# bitslot.net
KiCad netlist of a schematic drawn in Altium Designer
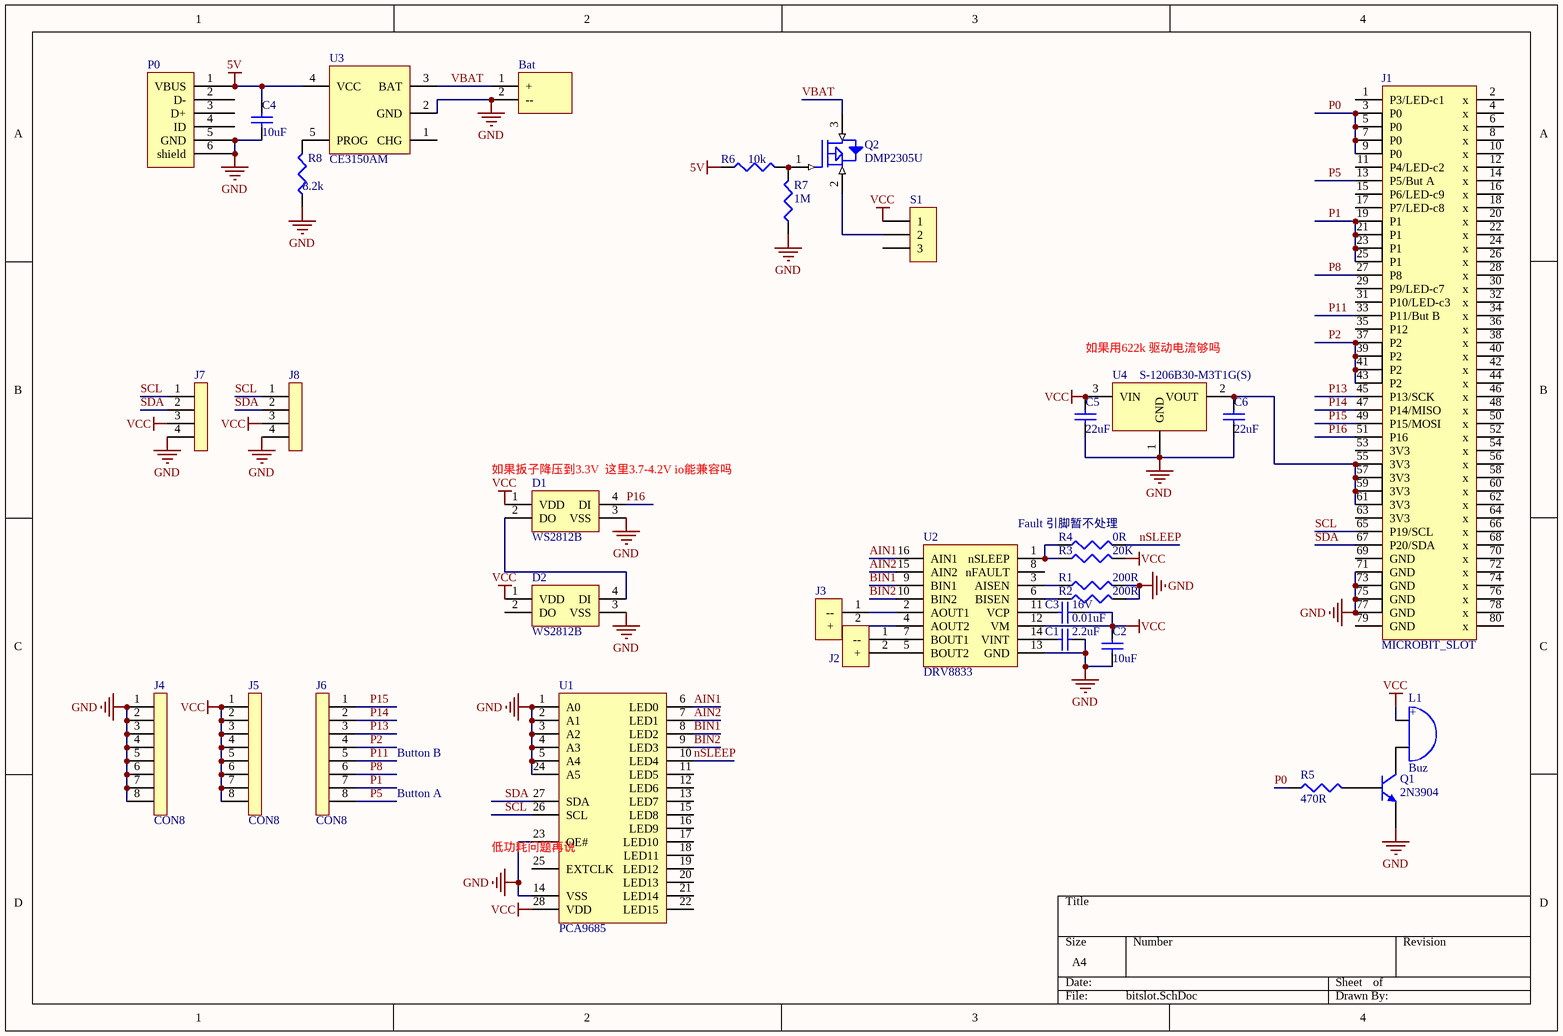
[diagram p0: bitslot.SchDoc]

(export (version "E")
  (design (tool "Eeschema 10.0.6"))
  (components
    (comp (ref "Bat")
      (value "~")
      (footprint "BAT-2040")
      (description "2x4cm Li-bat")
      (libsource (lib "misc1") (part "Battery2040"))
    )
    (comp (ref "C1")
      (value "2.2uF")
      (footprint "C0603")
      (fields (field (name "PUBLISHER") "Altium Limited"))
      (libsource (lib "misc") (part "Cap"))
    )
    (comp (ref "C2")
      (value "10uF")
      (footprint "C0603")
      (fields (field (name "PUBLISHER") "Altium Limited"))
      (libsource (lib "misc") (part "Cap"))
    )
    (comp (ref "C3")
      (value "16V")
      (footprint "C0603")
      (fields (field (name "ALTIUM_VALUE") "0.01uF") (field (name "PUBLISHER") "Altium Limited"))
      (libsource (lib "misc") (part "Cap"))
    )
    (comp (ref "C4")
      (value "10uF")
      (footprint "C0603")
      (fields (field (name "PUBLISHER") "Altium Limited"))
      (libsource (lib "misc") (part "Cap"))
    )
    (comp (ref "C5")
      (value "22uF")
      (footprint "C0603")
      (fields (field (name "PUBLISHER") "Altium Limited"))
      (libsource (lib "misc") (part "Cap"))
    )
    (comp (ref "C6")
      (value "22uF")
      (footprint "C0603")
      (fields (field (name "PUBLISHER") "Altium Limited"))
      (libsource (lib "misc") (part "Cap"))
    )
    (comp (ref "D1") (value "WS2812B") (footprint "WS2812B") (libsource (lib "misc1") (part "WS2812B")))
    (comp (ref "D2") (value "WS2812B") (footprint "WS2812B") (libsource (lib "misc1") (part "WS2812B")))
    (comp (ref "J1")
      (value "MICROBIT_SLOT")
      (footprint "microbit_slot")
      (libsource (lib "misc1") (part "MICROBIT_SLOT"))
    )
    (comp (ref "J2") (value "~") (footprint "S2B-PH-K-S") (libsource (lib "misc") (part "CON2_power")))
    (comp (ref "J3") (value "~") (footprint "S2B-PH-K-S") (libsource (lib "misc") (part "CON2_power")))
    (comp (ref "J4") (value "CON8") (footprint "CON8") (libsource (lib "misc") (part "CON8")))
    (comp (ref "J5") (value "CON8") (footprint "CON8") (libsource (lib "misc") (part "CON8")))
    (comp (ref "J6") (value "CON8") (footprint "CON8") (libsource (lib "") (part "CON8_1")))
    (comp (ref "J7") (value "~") (footprint "CON4") (libsource (lib "misc") (part "CON4")))
    (comp (ref "J8") (value "~") (footprint "CON4") (libsource (lib "misc") (part "CON4")))
    (comp (ref "L1")
      (value "Buz")
      (footprint "Buzzer")
      (fields (field (name "PUBLISHER") "Altium Limited"))
      (libsource (lib "misc") (part "Buzzer"))
    )
    (comp (ref "P0") (value "~") (footprint "USB_MICRO") (libsource (lib "Switcher") (part "micro_usb")))
    (comp (ref "Q1")
      (value "2N3904")
      (footprint "SOT23-3")
      (description "NPN General Purpose Amplifier")
      (fields (field (name "PUBLISHER") "Altium Limited"))
      (libsource (lib "misc") (part "2N3904"))
    )
    (comp (ref "Q2") (value "DMP2305U") (footprint "SOT23-3") (libsource (lib "misc") (part "MOSFET P")))
    (comp (ref "R1")
      (value "200R")
      (footprint "R0603")
      (fields (field (name "PUBLISHER") "Altium Limited"))
      (libsource (lib "misc") (part "Res"))
    )
    (comp (ref "R2")
      (value "200R")
      (footprint "R0603")
      (fields (field (name "PUBLISHER") "Altium Limited"))
      (libsource (lib "misc") (part "Res"))
    )
    (comp (ref "R3")
      (value "20K")
      (footprint "R0603")
      (fields (field (name "PUBLISHER") "Altium Limited"))
      (libsource (lib "misc") (part "Res"))
    )
    (comp (ref "R4")
      (value "0R")
      (footprint "R0603")
      (fields (field (name "PUBLISHER") "Altium Limited"))
      (libsource (lib "misc") (part "Res"))
    )
    (comp (ref "R5")
      (value "470R")
      (footprint "R0603")
      (fields (field (name "PUBLISHER") "Altium Limited"))
      (libsource (lib "misc") (part "Res"))
    )
    (comp (ref "R6")
      (value "10k")
      (footprint "R0603")
      (fields (field (name "PUBLISHER") "Altium Limited"))
      (libsource (lib "misc") (part "Res"))
    )
    (comp (ref "R7")
      (value "1M")
      (footprint "R0603")
      (fields (field (name "PUBLISHER") "Altium Limited"))
      (libsource (lib "misc") (part "Res"))
    )
    (comp (ref "R8")
      (value "8.2k")
      (footprint "R0603")
      (fields (field (name "PUBLISHER") "Altium Limited"))
      (libsource (lib "misc") (part "Res"))
    )
    (comp (ref "S1")
      (value "~")
      (footprint "SWITCH-1")
      (description "Header, 3-Pin")
      (fields (field (name "PUBLISHER") "Altium Limited"))
      (libsource (lib "misc") (part "CON3"))
    )
    (comp (ref "U1") (value "PCA9685") (footprint "TSSOP-28") (libsource (lib "misc1") (part "PCA9685")))
    (comp (ref "U2")
      (value "DRV8833")
      (footprint "TSSOP-16")
      (description "TSSOP-16")
      (libsource (lib "misc1") (part "DRV8833"))
    )
    (comp (ref "U3")
      (value "CE3150AM")
      (footprint "SOT23-5")
      (description "LI-Ion battery charger with Thermal Regulation")
      (libsource (lib "misc") (part "CE3150AM"))
    )
    (comp (ref "U4")
      (value "S-1206B30-M3T1G(S)")
      (footprint "SOT23-3")
      (libsource (lib "dusun01-SCH") (part "S-1206BXX"))
    )
  )
  (nets
    (net (code "1") (name "/AIN1") (class "Default")
      (node (ref "U1") (pin "6") (pinfunction "LED0_6") (pintype "passive"))
      (node (ref "U2") (pin "16") (pinfunction "AIN1_16") (pintype "passive"))
    )
    (net (code "2") (name "/AIN2") (class "Default")
      (node (ref "U1") (pin "7") (pinfunction "LED1_7") (pintype "passive"))
      (node (ref "U2") (pin "15") (pinfunction "AIN2_15") (pintype "passive"))
    )
    (net (code "3") (name "/BIN1") (class "Default")
      (node (ref "U1") (pin "8") (pinfunction "LED2_8") (pintype "passive"))
      (node (ref "U2") (pin "9") (pinfunction "BIN1_9") (pintype "passive"))
    )
    (net (code "4") (name "/BIN2") (class "Default")
      (node (ref "U1") (pin "9") (pinfunction "LED3_9") (pintype "passive"))
      (node (ref "U2") (pin "10") (pinfunction "BIN2_10") (pintype "passive"))
    )
    (net (code "5") (name "/P0") (class "Default")
      (node (ref "J1") (pin "3") (pinfunction "P0_3") (pintype "passive"))
      (node (ref "J1") (pin "5") (pinfunction "P0_5") (pintype "passive"))
      (node (ref "J1") (pin "7") (pinfunction "P0_7") (pintype "passive"))
      (node (ref "J1") (pin "9") (pinfunction "P0_9") (pintype "passive"))
      (node (ref "R5") (pin "1") (pinfunction "1_1") (pintype "passive"))
    )
    (net (code "6") (name "/P1") (class "Default")
      (node (ref "J1") (pin "19") (pinfunction "P1_19") (pintype "passive"))
      (node (ref "J1") (pin "21") (pinfunction "P1_21") (pintype "passive"))
      (node (ref "J1") (pin "23") (pinfunction "P1_23") (pintype "passive"))
      (node (ref "J1") (pin "25") (pinfunction "P1_25") (pintype "passive"))
      (node (ref "J6") (pin "7") (pintype "passive"))
    )
    (net (code "7") (name "/P2") (class "Default")
      (node (ref "J1") (pin "37") (pinfunction "P2_37") (pintype "passive"))
      (node (ref "J1") (pin "39") (pinfunction "P2_39") (pintype "passive"))
      (node (ref "J1") (pin "41") (pinfunction "P2_41") (pintype "passive"))
      (node (ref "J1") (pin "43") (pinfunction "P2_43") (pintype "passive"))
      (node (ref "J6") (pin "4") (pintype "passive"))
    )
    (net (code "8") (name "/P5") (class "Default")
      (node (ref "J1") (pin "13") (pinfunction "P5/But_A_13") (pintype "passive"))
      (node (ref "J6") (pin "8") (pintype "passive"))
    )
    (net (code "9") (name "/P8") (class "Default")
      (node (ref "J1") (pin "27") (pinfunction "P8_27") (pintype "passive"))
      (node (ref "J6") (pin "6") (pintype "passive"))
    )
    (net (code "10") (name "/P11") (class "Default")
      (node (ref "J1") (pin "33") (pinfunction "P11/But_B_33") (pintype "passive"))
      (node (ref "J6") (pin "5") (pintype "passive"))
    )
    (net (code "11") (name "/P13") (class "Default")
      (node (ref "J1") (pin "45") (pinfunction "P13/SCK_45") (pintype "passive"))
      (node (ref "J6") (pin "3") (pintype "passive"))
    )
    (net (code "12") (name "/P14") (class "Default")
      (node (ref "J1") (pin "47") (pinfunction "P14/MISO_47") (pintype "passive"))
      (node (ref "J6") (pin "2") (pintype "passive"))
    )
    (net (code "13") (name "/P15") (class "Default")
      (node (ref "J1") (pin "49") (pinfunction "P15/MOSI_49") (pintype "passive"))
      (node (ref "J6") (pin "1") (pintype "passive"))
    )
    (net (code "14") (name "/P16") (class "Default")
      (node (ref "D1") (pin "4") (pinfunction "DI_4") (pintype "passive"))
      (node (ref "J1") (pin "51") (pinfunction "P16_51") (pintype "passive"))
    )
    (net (code "15") (name "/SCL") (class "Default")
      (node (ref "J1") (pin "65") (pinfunction "P19/SCL_65") (pintype "passive"))
      (node (ref "J7") (pin "1") (pintype "passive"))
      (node (ref "J8") (pin "1") (pintype "passive"))
      (node (ref "U1") (pin "26") (pinfunction "SCL_26") (pintype "passive"))
    )
    (net (code "16") (name "/SDA") (class "Default")
      (node (ref "J1") (pin "67") (pinfunction "P20/SDA_67") (pintype "passive"))
      (node (ref "J7") (pin "2") (pintype "passive"))
      (node (ref "J8") (pin "2") (pintype "passive"))
      (node (ref "U1") (pin "27") (pinfunction "SDA_27") (pintype "passive"))
    )
    (net (code "17") (name "/VBAT") (class "Default")
      (node (ref "Bat") (pin "1") (pinfunction "+_1") (pintype "passive"))
      (node (ref "Q2") (pin "3") (pinfunction "D_3") (pintype "input"))
      (node (ref "U3") (pin "3") (pinfunction "BAT_3") (pintype "passive"))
    )
    (net (code "18") (name "/nSLEEP") (class "Default")
      (node (ref "R4") (pin "2") (pinfunction "2_2") (pintype "passive"))
      (node (ref "U1") (pin "10") (pinfunction "LED4_10") (pintype "passive"))
    )
    (net (code "19") (name "5V") (class "Default")
      (node (ref "C4") (pin "2") (pinfunction "2_2") (pintype "passive"))
      (node (ref "P0") (pin "1") (pinfunction "VBUS_1") (pintype "passive"))
      (node (ref "R6") (pin "1") (pinfunction "1_1") (pintype "passive"))
      (node (ref "U3") (pin "4") (pinfunction "VCC_4") (pintype "passive"))
    )
    (net (code "20") (name "GND") (class "Default")
      (node (ref "Bat") (pin "2") (pinfunction "--_2") (pintype "passive"))
      (node (ref "C1") (pin "2") (pinfunction "2_2") (pintype "passive"))
      (node (ref "C2") (pin "1") (pinfunction "1_1") (pintype "passive"))
      (node (ref "C4") (pin "1") (pinfunction "1_1") (pintype "passive"))
      (node (ref "C5") (pin "1") (pinfunction "1_1") (pintype "passive"))
      (node (ref "C6") (pin "1") (pinfunction "1_1") (pintype "passive"))
      (node (ref "D1") (pin "3") (pinfunction "VSS_3") (pintype "passive"))
      (node (ref "D2") (pin "3") (pinfunction "VSS_3") (pintype "passive"))
      (node (ref "J1") (pin "71") (pinfunction "GND_71") (pintype "passive"))
      (node (ref "J1") (pin "73") (pinfunction "GND_73") (pintype "passive"))
      (node (ref "J1") (pin "75") (pinfunction "GND_75") (pintype "passive"))
      (node (ref "J1") (pin "77") (pinfunction "GND_77") (pintype "passive"))
      (node (ref "J4") (pin "1") (pintype "passive"))
      (node (ref "J4") (pin "2") (pintype "passive"))
      (node (ref "J4") (pin "3") (pintype "passive"))
      (node (ref "J4") (pin "4") (pintype "passive"))
      (node (ref "J4") (pin "5") (pintype "passive"))
      (node (ref "J4") (pin "6") (pintype "passive"))
      (node (ref "J4") (pin "7") (pintype "passive"))
      (node (ref "J4") (pin "8") (pintype "passive"))
      (node (ref "J7") (pin "4") (pintype "passive"))
      (node (ref "J8") (pin "4") (pintype "passive"))
      (node (ref "P0") (pin "5") (pinfunction "GND_5") (pintype "passive"))
      (node (ref "P0") (pin "6") (pinfunction "shield_6") (pintype "passive"))
      (node (ref "Q1") (pin "1") (pinfunction "E_1") (pintype "passive"))
      (node (ref "R1") (pin "2") (pinfunction "2_2") (pintype "passive"))
      (node (ref "R2") (pin "2") (pinfunction "2_2") (pintype "passive"))
      (node (ref "R7") (pin "1") (pinfunction "1_1") (pintype "passive"))
      (node (ref "R8") (pin "1") (pinfunction "1_1") (pintype "passive"))
      (node (ref "U1") (pin "1") (pinfunction "A0_1") (pintype "passive"))
      (node (ref "U1") (pin "14") (pinfunction "VSS_14") (pintype "passive"))
      (node (ref "U1") (pin "2") (pinfunction "A1_2") (pintype "passive"))
      (node (ref "U1") (pin "23") (pinfunction "OE#_23") (pintype "passive"))
      (node (ref "U1") (pin "24") (pinfunction "A5_24") (pintype "passive"))
      (node (ref "U1") (pin "3") (pinfunction "A2_3") (pintype "passive"))
      (node (ref "U1") (pin "4") (pinfunction "A3_4") (pintype "passive"))
      (node (ref "U1") (pin "5") (pinfunction "A4_5") (pintype "passive"))
      (node (ref "U2") (pin "13") (pinfunction "GND_13") (pintype "passive"))
      (node (ref "U3") (pin "2") (pinfunction "GND_2") (pintype "passive"))
      (node (ref "U4") (pin "1") (pinfunction "GND_1") (pintype "passive"))
    )
    (net (code "21") (name "Net-(D1-DO)") (class "Default")
      (node (ref "D1") (pin "2") (pinfunction "DO_2") (pintype "passive"))
      (node (ref "D2") (pin "4") (pinfunction "DI_4") (pintype "passive"))
    )
    (net (code "22") (name "Net-(J2-+)") (class "Default")
      (node (ref "J2") (pin "2") (pinfunction "+_2") (pintype "passive"))
      (node (ref "U2") (pin "5") (pinfunction "BOUT2_5") (pintype "passive"))
    )
    (net (code "23") (name "Net-(J2---)") (class "Default")
      (node (ref "J2") (pin "1") (pinfunction "--_1") (pintype "passive"))
      (node (ref "U2") (pin "7") (pinfunction "BOUT1_7") (pintype "passive"))
    )
    (net (code "24") (name "Net-(J3-+)") (class "Default")
      (node (ref "J3") (pin "2") (pinfunction "+_2") (pintype "passive"))
      (node (ref "U2") (pin "4") (pinfunction "AOUT2_4") (pintype "passive"))
    )
    (net (code "25") (name "Net-(J3---)") (class "Default")
      (node (ref "J3") (pin "1") (pinfunction "--_1") (pintype "passive"))
      (node (ref "U2") (pin "2") (pinfunction "AOUT1_2") (pintype "passive"))
    )
    (net (code "26") (name "Net-(L1-B)") (class "Default")
      (node (ref "L1") (pin "2") (pinfunction "B_2") (pintype "passive"))
      (node (ref "Q1") (pin "3") (pinfunction "C_3") (pintype "passive"))
    )
    (net (code "27") (name "Net-(Q1-B)") (class "Default")
      (node (ref "Q1") (pin "2") (pinfunction "B_2") (pintype "passive"))
      (node (ref "R5") (pin "2") (pinfunction "2_2") (pintype "passive"))
    )
    (net (code "28") (name "Net-(Q2-G)") (class "Default")
      (node (ref "Q2") (pin "1") (pinfunction "G_1") (pintype "input"))
      (node (ref "R6") (pin "2") (pinfunction "2_2") (pintype "passive"))
      (node (ref "R7") (pin "2") (pinfunction "2_2") (pintype "passive"))
    )
    (net (code "29") (name "Net-(Q2-S)") (class "Default")
      (node (ref "Q2") (pin "2") (pinfunction "S_2") (pintype "input"))
      (node (ref "S1") (pin "2") (pinfunction "2_2") (pintype "passive"))
    )
    (net (code "30") (name "Net-(U2-AISEN)") (class "Default")
      (node (ref "R1") (pin "1") (pinfunction "1_1") (pintype "passive"))
      (node (ref "U2") (pin "3") (pinfunction "AISEN_3") (pintype "passive"))
    )
    (net (code "31") (name "Net-(U2-BISEN)") (class "Default")
      (node (ref "R2") (pin "1") (pinfunction "1_1") (pintype "passive"))
      (node (ref "U2") (pin "6") (pinfunction "BISEN_6") (pintype "passive"))
    )
    (net (code "32") (name "Net-(U2-VCP)") (class "Default")
      (node (ref "C3") (pin "1") (pinfunction "1_1") (pintype "passive"))
      (node (ref "U2") (pin "11") (pinfunction "VCP_11") (pintype "passive"))
    )
    (net (code "33") (name "Net-(U2-VINT)") (class "Default")
      (node (ref "C1") (pin "1") (pinfunction "1_1") (pintype "passive"))
      (node (ref "U2") (pin "14") (pinfunction "VINT_14") (pintype "passive"))
    )
    (net (code "34") (name "Net-(U2-nSLEEP)") (class "Default")
      (node (ref "R3") (pin "1") (pinfunction "1_1") (pintype "passive"))
      (node (ref "R4") (pin "1") (pinfunction "1_1") (pintype "passive"))
      (node (ref "U2") (pin "1") (pinfunction "nSLEEP_1") (pintype "passive"))
    )
    (net (code "35") (name "Net-(U3-PROG)") (class "Default")
      (node (ref "R8") (pin "2") (pinfunction "2_2") (pintype "passive"))
      (node (ref "U3") (pin "5") (pinfunction "PROG_5") (pintype "passive"))
    )
    (net (code "36") (name "Net-(U4-VOUT)") (class "Default")
      (node (ref "C6") (pin "2") (pinfunction "2_2") (pintype "passive"))
      (node (ref "J1") (pin "55") (pinfunction "3V3_55") (pintype "passive"))
      (node (ref "J1") (pin "57") (pinfunction "3V3_57") (pintype "passive"))
      (node (ref "J1") (pin "59") (pinfunction "3V3_59") (pintype "passive"))
      (node (ref "J1") (pin "61") (pinfunction "3V3_61") (pintype "passive"))
      (node (ref "U4") (pin "2") (pinfunction "VOUT_2") (pintype "passive"))
    )
    (net (code "37") (name "VCC") (class "Default")
      (node (ref "C2") (pin "2") (pinfunction "2_2") (pintype "passive"))
      (node (ref "C3") (pin "2") (pinfunction "2_2") (pintype "passive"))
      (node (ref "C5") (pin "2") (pinfunction "2_2") (pintype "passive"))
      (node (ref "D1") (pin "1") (pinfunction "VDD_1") (pintype "passive"))
      (node (ref "D2") (pin "1") (pinfunction "VDD_1") (pintype "passive"))
      (node (ref "J5") (pin "1") (pintype "passive"))
      (node (ref "J5") (pin "2") (pintype "passive"))
      (node (ref "J5") (pin "3") (pintype "passive"))
      (node (ref "J5") (pin "4") (pintype "passive"))
      (node (ref "J5") (pin "5") (pintype "passive"))
      (node (ref "J5") (pin "6") (pintype "passive"))
      (node (ref "J5") (pin "7") (pintype "passive"))
      (node (ref "J5") (pin "8") (pintype "passive"))
      (node (ref "J7") (pin "3") (pintype "passive"))
      (node (ref "J8") (pin "3") (pintype "passive"))
      (node (ref "L1") (pin "1") (pinfunction "A_1") (pintype "passive"))
      (node (ref "R3") (pin "2") (pinfunction "2_2") (pintype "passive"))
      (node (ref "S1") (pin "1") (pinfunction "1_1") (pintype "passive"))
      (node (ref "U1") (pin "28") (pinfunction "VDD_28") (pintype "passive"))
      (node (ref "U2") (pin "12") (pinfunction "VM_12") (pintype "passive"))
      (node (ref "U4") (pin "3") (pinfunction "VIN_3") (pintype "passive"))
    )
    (net (code "38") (name "unconnected-(D2-DO-Pad2)") (class "Default")
      (node (ref "D2") (pin "2") (pinfunction "DO_2") (pintype "passive"))
    )
    (net (code "39") (name "unconnected-(J1-3V3-Pad53)") (class "Default")
      (node (ref "J1") (pin "53") (pinfunction "3V3_53") (pintype "passive"))
    )
    (net (code "40") (name "unconnected-(J1-3V3-Pad63)") (class "Default")
      (node (ref "J1") (pin "63") (pinfunction "3V3_63") (pintype "passive"))
    )
    (net (code "41") (name "unconnected-(J1-GND-Pad69)") (class "Default")
      (node (ref "J1") (pin "69") (pinfunction "GND_69") (pintype "passive"))
    )
    (net (code "42") (name "unconnected-(J1-GND-Pad79)") (class "Default")
      (node (ref "J1") (pin "79") (pinfunction "GND_79") (pintype "passive"))
    )
    (net (code "43") (name "unconnected-(J1-P3{slash}LED-c1-Pad1)") (class "Default")
      (node (ref "J1") (pin "1") (pinfunction "P3/LED-c1_1") (pintype "passive"))
    )
    (net (code "44") (name "unconnected-(J1-P4{slash}LED-c2-Pad11)") (class "Default")
      (node (ref "J1") (pin "11") (pinfunction "P4/LED-c2_11") (pintype "passive"))
    )
    (net (code "45") (name "unconnected-(J1-P6{slash}LED-c9-Pad15)") (class "Default")
      (node (ref "J1") (pin "15") (pinfunction "P6/LED-c9_15") (pintype "passive"))
    )
    (net (code "46") (name "unconnected-(J1-P7{slash}LED-c8-Pad17)") (class "Default")
      (node (ref "J1") (pin "17") (pinfunction "P7/LED-c8_17") (pintype "passive"))
    )
    (net (code "47") (name "unconnected-(J1-P9{slash}LED-c7-Pad29)") (class "Default")
      (node (ref "J1") (pin "29") (pinfunction "P9/LED-c7_29") (pintype "passive"))
    )
    (net (code "48") (name "unconnected-(J1-P10{slash}LED-c3-Pad31)") (class "Default")
      (node (ref "J1") (pin "31") (pinfunction "P10/LED-c3_31") (pintype "passive"))
    )
    (net (code "49") (name "unconnected-(J1-P12-Pad35)") (class "Default")
      (node (ref "J1") (pin "35") (pinfunction "P12_35") (pintype "passive"))
    )
    (net (code "50") (name "unconnected-(J1-x-Pad2)") (class "Default")
      (node (ref "J1") (pin "2") (pinfunction "x_2") (pintype "passive"))
    )
    (net (code "51") (name "unconnected-(J1-x-Pad4)") (class "Default")
      (node (ref "J1") (pin "4") (pinfunction "x_4") (pintype "passive"))
    )
    (net (code "52") (name "unconnected-(J1-x-Pad6)") (class "Default")
      (node (ref "J1") (pin "6") (pinfunction "x_6") (pintype "passive"))
    )
    (net (code "53") (name "unconnected-(J1-x-Pad8)") (class "Default")
      (node (ref "J1") (pin "8") (pinfunction "x_8") (pintype "passive"))
    )
    (net (code "54") (name "unconnected-(J1-x-Pad10)") (class "Default")
      (node (ref "J1") (pin "10") (pinfunction "x_10") (pintype "passive"))
    )
    (net (code "55") (name "unconnected-(J1-x-Pad12)") (class "Default")
      (node (ref "J1") (pin "12") (pinfunction "x_12") (pintype "passive"))
    )
    (net (code "56") (name "unconnected-(J1-x-Pad14)") (class "Default")
      (node (ref "J1") (pin "14") (pinfunction "x_14") (pintype "passive"))
    )
    (net (code "57") (name "unconnected-(J1-x-Pad16)") (class "Default")
      (node (ref "J1") (pin "16") (pinfunction "x_16") (pintype "passive"))
    )
    (net (code "58") (name "unconnected-(J1-x-Pad18)") (class "Default")
      (node (ref "J1") (pin "18") (pinfunction "x_18") (pintype "passive"))
    )
    (net (code "59") (name "unconnected-(J1-x-Pad20)") (class "Default")
      (node (ref "J1") (pin "20") (pinfunction "x_20") (pintype "passive"))
    )
    (net (code "60") (name "unconnected-(J1-x-Pad22)") (class "Default")
      (node (ref "J1") (pin "22") (pinfunction "x_22") (pintype "passive"))
    )
    (net (code "61") (name "unconnected-(J1-x-Pad24)") (class "Default")
      (node (ref "J1") (pin "24") (pinfunction "x_24") (pintype "passive"))
    )
    (net (code "62") (name "unconnected-(J1-x-Pad26)") (class "Default")
      (node (ref "J1") (pin "26") (pinfunction "x_26") (pintype "passive"))
    )
    (net (code "63") (name "unconnected-(J1-x-Pad28)") (class "Default")
      (node (ref "J1") (pin "28") (pinfunction "x_28") (pintype "passive"))
    )
    (net (code "64") (name "unconnected-(J1-x-Pad30)") (class "Default")
      (node (ref "J1") (pin "30") (pinfunction "x_30") (pintype "passive"))
    )
    (net (code "65") (name "unconnected-(J1-x-Pad32)") (class "Default")
      (node (ref "J1") (pin "32") (pinfunction "x_32") (pintype "passive"))
    )
    (net (code "66") (name "unconnected-(J1-x-Pad34)") (class "Default")
      (node (ref "J1") (pin "34") (pinfunction "x_34") (pintype "passive"))
    )
    (net (code "67") (name "unconnected-(J1-x-Pad36)") (class "Default")
      (node (ref "J1") (pin "36") (pinfunction "x_36") (pintype "passive"))
    )
    (net (code "68") (name "unconnected-(J1-x-Pad38)") (class "Default")
      (node (ref "J1") (pin "38") (pinfunction "x_38") (pintype "passive"))
    )
    (net (code "69") (name "unconnected-(J1-x-Pad40)") (class "Default")
      (node (ref "J1") (pin "40") (pinfunction "x_40") (pintype "passive"))
    )
    (net (code "70") (name "unconnected-(J1-x-Pad42)") (class "Default")
      (node (ref "J1") (pin "42") (pinfunction "x_42") (pintype "passive"))
    )
    (net (code "71") (name "unconnected-(J1-x-Pad44)") (class "Default")
      (node (ref "J1") (pin "44") (pinfunction "x_44") (pintype "passive"))
    )
    (net (code "72") (name "unconnected-(J1-x-Pad46)") (class "Default")
      (node (ref "J1") (pin "46") (pinfunction "x_46") (pintype "passive"))
    )
    (net (code "73") (name "unconnected-(J1-x-Pad48)") (class "Default")
      (node (ref "J1") (pin "48") (pinfunction "x_48") (pintype "passive"))
    )
    (net (code "74") (name "unconnected-(J1-x-Pad50)") (class "Default")
      (node (ref "J1") (pin "50") (pinfunction "x_50") (pintype "passive"))
    )
    (net (code "75") (name "unconnected-(J1-x-Pad52)") (class "Default")
      (node (ref "J1") (pin "52") (pinfunction "x_52") (pintype "passive"))
    )
    (net (code "76") (name "unconnected-(J1-x-Pad54)") (class "Default")
      (node (ref "J1") (pin "54") (pinfunction "x_54") (pintype "passive"))
    )
    (net (code "77") (name "unconnected-(J1-x-Pad56)") (class "Default")
      (node (ref "J1") (pin "56") (pinfunction "x_56") (pintype "passive"))
    )
    (net (code "78") (name "unconnected-(J1-x-Pad58)") (class "Default")
      (node (ref "J1") (pin "58") (pinfunction "x_58") (pintype "passive"))
    )
    (net (code "79") (name "unconnected-(J1-x-Pad60)") (class "Default")
      (node (ref "J1") (pin "60") (pinfunction "x_60") (pintype "passive"))
    )
    (net (code "80") (name "unconnected-(J1-x-Pad62)") (class "Default")
      (node (ref "J1") (pin "62") (pinfunction "x_62") (pintype "passive"))
    )
    (net (code "81") (name "unconnected-(J1-x-Pad64)") (class "Default")
      (node (ref "J1") (pin "64") (pinfunction "x_64") (pintype "passive"))
    )
    (net (code "82") (name "unconnected-(J1-x-Pad66)") (class "Default")
      (node (ref "J1") (pin "66") (pinfunction "x_66") (pintype "passive"))
    )
    (net (code "83") (name "unconnected-(J1-x-Pad68)") (class "Default")
      (node (ref "J1") (pin "68") (pinfunction "x_68") (pintype "passive"))
    )
    (net (code "84") (name "unconnected-(J1-x-Pad70)") (class "Default")
      (node (ref "J1") (pin "70") (pinfunction "x_70") (pintype "passive"))
    )
    (net (code "85") (name "unconnected-(J1-x-Pad72)") (class "Default")
      (node (ref "J1") (pin "72") (pinfunction "x_72") (pintype "passive"))
    )
    (net (code "86") (name "unconnected-(J1-x-Pad74)") (class "Default")
      (node (ref "J1") (pin "74") (pinfunction "x_74") (pintype "passive"))
    )
    (net (code "87") (name "unconnected-(J1-x-Pad76)") (class "Default")
      (node (ref "J1") (pin "76") (pinfunction "x_76") (pintype "passive"))
    )
    (net (code "88") (name "unconnected-(J1-x-Pad78)") (class "Default")
      (node (ref "J1") (pin "78") (pinfunction "x_78") (pintype "passive"))
    )
    (net (code "89") (name "unconnected-(J1-x-Pad80)") (class "Default")
      (node (ref "J1") (pin "80") (pinfunction "x_80") (pintype "passive"))
    )
    (net (code "90") (name "unconnected-(P0-D+-Pad3)") (class "Default")
      (node (ref "P0") (pin "3") (pinfunction "D+_3") (pintype "passive"))
    )
    (net (code "91") (name "unconnected-(P0-D--Pad2)") (class "Default")
      (node (ref "P0") (pin "2") (pinfunction "D-_2") (pintype "passive"))
    )
    (net (code "92") (name "unconnected-(P0-ID-Pad4)") (class "Default")
      (node (ref "P0") (pin "4") (pinfunction "ID_4") (pintype "passive"))
    )
    (net (code "93") (name "unconnected-(S1-Pad3)") (class "Default")
      (node (ref "S1") (pin "3") (pinfunction "3_3") (pintype "passive"))
    )
    (net (code "94") (name "unconnected-(U1-EXTCLK-Pad25)") (class "Default")
      (node (ref "U1") (pin "25") (pinfunction "EXTCLK_25") (pintype "passive"))
    )
    (net (code "95") (name "unconnected-(U1-LED5-Pad11)") (class "Default")
      (node (ref "U1") (pin "11") (pinfunction "LED5_11") (pintype "passive"))
    )
    (net (code "96") (name "unconnected-(U1-LED6-Pad12)") (class "Default")
      (node (ref "U1") (pin "12") (pinfunction "LED6_12") (pintype "passive"))
    )
    (net (code "97") (name "unconnected-(U1-LED7-Pad13)") (class "Default")
      (node (ref "U1") (pin "13") (pinfunction "LED7_13") (pintype "passive"))
    )
    (net (code "98") (name "unconnected-(U1-LED8-Pad15)") (class "Default")
      (node (ref "U1") (pin "15") (pinfunction "LED8_15") (pintype "passive"))
    )
    (net (code "99") (name "unconnected-(U1-LED9-Pad16)") (class "Default")
      (node (ref "U1") (pin "16") (pinfunction "LED9_16") (pintype "passive"))
    )
    (net (code "100") (name "unconnected-(U1-LED10-Pad17)") (class "Default")
      (node (ref "U1") (pin "17") (pinfunction "LED10_17") (pintype "passive"))
    )
    (net (code "101") (name "unconnected-(U1-LED11-Pad18)") (class "Default")
      (node (ref "U1") (pin "18") (pinfunction "LED11_18") (pintype "passive"))
    )
    (net (code "102") (name "unconnected-(U1-LED12-Pad19)") (class "Default")
      (node (ref "U1") (pin "19") (pinfunction "LED12_19") (pintype "passive"))
    )
    (net (code "103") (name "unconnected-(U1-LED13-Pad20)") (class "Default")
      (node (ref "U1") (pin "20") (pinfunction "LED13_20") (pintype "passive"))
    )
    (net (code "104") (name "unconnected-(U1-LED14-Pad21)") (class "Default")
      (node (ref "U1") (pin "21") (pinfunction "LED14_21") (pintype "passive"))
    )
    (net (code "105") (name "unconnected-(U1-LED15-Pad22)") (class "Default")
      (node (ref "U1") (pin "22") (pinfunction "LED15_22") (pintype "passive"))
    )
    (net (code "106") (name "unconnected-(U2-nFAULT-Pad8)") (class "Default")
      (node (ref "U2") (pin "8") (pinfunction "nFAULT_8") (pintype "passive"))
    )
    (net (code "107") (name "unconnected-(U3-CHG-Pad1)") (class "Default")
      (node (ref "U3") (pin "1") (pinfunction "CHG_1") (pintype "passive"))
    )
  )
)
